# sparrow-though-jack.net
KiCad netlist of a schematic drawn in EAGLE
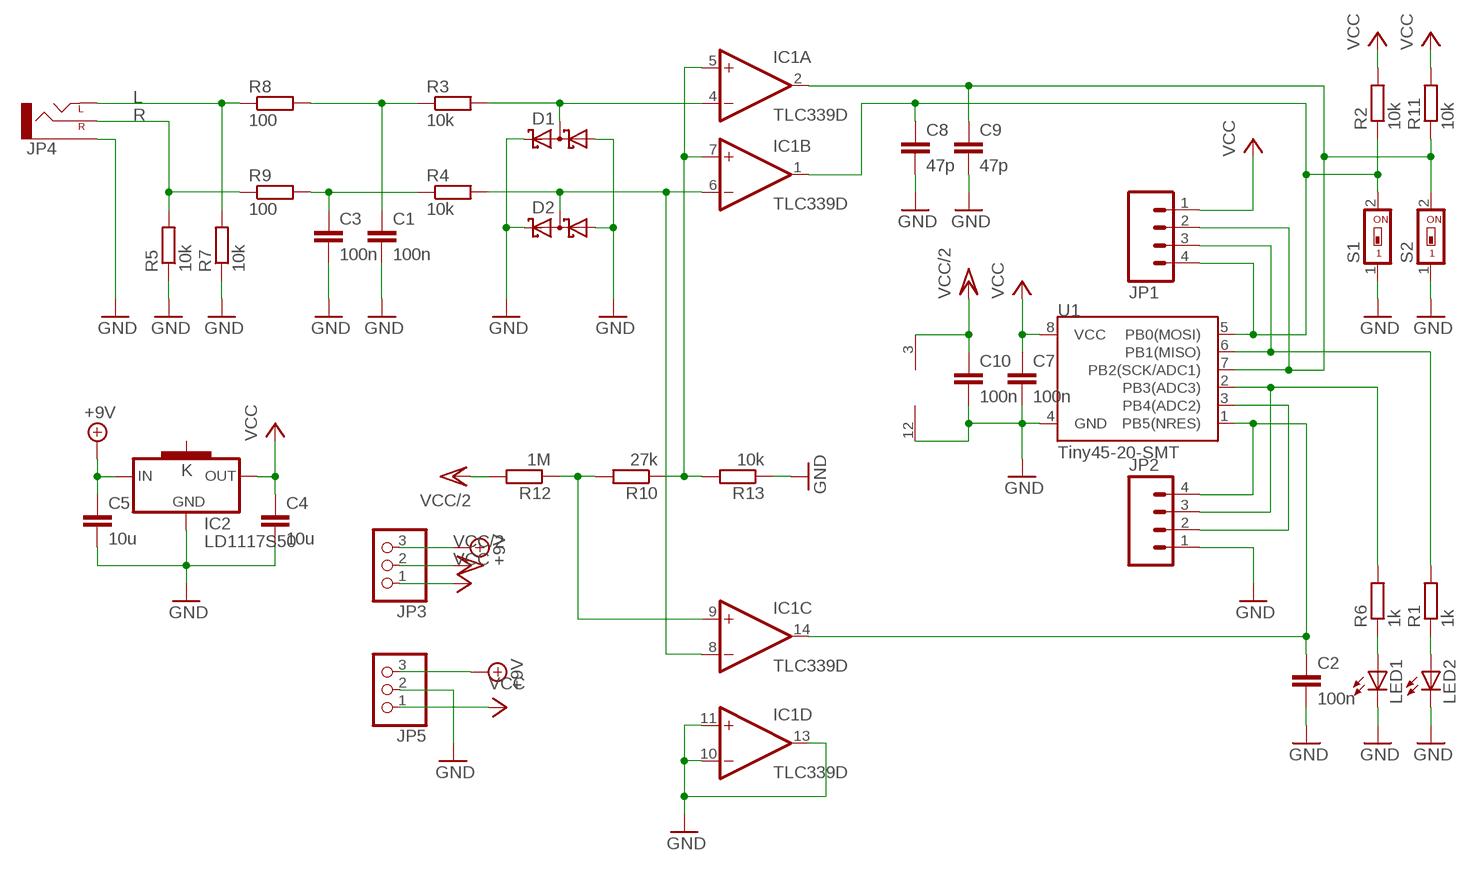
[diagram p0: schematic, sheet 1]

(export (version "E")
  (design (tool "Eeschema 10.0.6"))
  (components
    (comp (ref "C1")
      (value "100n")
      (footprint "eagle-import:C0805K")
      (libsource (lib "eagle-import") (part "C-EUC0805K"))
    )
    (comp (ref "C2")
      (value "100n")
      (footprint "eagle-import:C0805K")
      (libsource (lib "eagle-import") (part "C-EUC0805K"))
    )
    (comp (ref "C3")
      (value "100n")
      (footprint "eagle-import:C0805K")
      (libsource (lib "eagle-import") (part "C-EUC0805K"))
    )
    (comp (ref "C4")
      (value "10u")
      (footprint "eagle-import:C0805K")
      (libsource (lib "eagle-import") (part "C-EUC0805K"))
    )
    (comp (ref "C5")
      (value "10u")
      (footprint "eagle-import:C0805K")
      (libsource (lib "eagle-import") (part "C-EUC0805K"))
    )
    (comp (ref "C7")
      (value "100n")
      (footprint "eagle-import:C0805K")
      (libsource (lib "eagle-import") (part "C-EUC0805K"))
    )
    (comp (ref "C8")
      (value "47p")
      (footprint "eagle-import:C0805K")
      (libsource (lib "eagle-import") (part "C-EUC0805K"))
    )
    (comp (ref "C9")
      (value "47p")
      (footprint "eagle-import:C0805K")
      (libsource (lib "eagle-import") (part "C-EUC0805K"))
    )
    (comp (ref "C10")
      (value "100n")
      (footprint "eagle-import:C0805K")
      (libsource (lib "eagle-import") (part "C-EUC0805K"))
    )
    (comp (ref "D1")
      (value "BAT54S")
      (footprint "eagle-import:SOT23")
      (libsource (lib "eagle-import") (part "BAT54S"))
    )
    (comp (ref "D2")
      (value "BAT54S")
      (footprint "eagle-import:SOT23")
      (libsource (lib "eagle-import") (part "BAT54S"))
    )
    (comp (ref "IC1")
      (value "TLC339D")
      (footprint "eagle-import:SO14")
      (libsource (lib "eagle-import") (part "TLC339D"))
    )
    (comp (ref "IC2")
      (value "LD1117S50")
      (footprint "eagle-import:SOT223")
      (libsource (lib "eagle-import") (part "LD1117S50"))
    )
    (comp (ref "JP1")
      (value "M04PTH")
      (footprint "eagle-import:1X04")
      (libsource (lib "eagle-import") (part "M04PTH"))
    )
    (comp (ref "JP2")
      (value "M04PTH")
      (footprint "eagle-import:1X04")
      (libsource (lib "eagle-import") (part "M04PTH"))
    )
    (comp (ref "JP3")
      (value "PINHD-1X3")
      (footprint "eagle-import:1X03")
      (libsource (lib "eagle-import") (part "PINHD-1X3"))
    )
    (comp (ref "JP4")
      (value "AUDIO-JACKPIN-HOLES")
      (footprint "eagle-import:AUDIO-JACK-HOLES")
      (libsource (lib "eagle-import") (part "AUDIO-JACKPIN-HOLES"))
    )
    (comp (ref "JP5")
      (value "PINHD-1X3")
      (footprint "eagle-import:1X03")
      (libsource (lib "eagle-import") (part "PINHD-1X3"))
    )
    (comp (ref "LED1")
      (value "LEDCHIP-LED0805")
      (footprint "eagle-import:CHIP-LED0805")
      (libsource (lib "eagle-import") (part "LEDCHIP-LED0805"))
    )
    (comp (ref "LED2")
      (value "LEDCHIP-LED0805")
      (footprint "eagle-import:CHIP-LED0805")
      (libsource (lib "eagle-import") (part "LEDCHIP-LED0805"))
    )
    (comp (ref "R1")
      (value "1k")
      (footprint "eagle-import:M0805")
      (libsource (lib "eagle-import") (part "R-EU_M0805"))
    )
    (comp (ref "R2")
      (value "10k")
      (footprint "eagle-import:M0805")
      (libsource (lib "eagle-import") (part "R-EU_M0805"))
    )
    (comp (ref "R3")
      (value "10k")
      (footprint "eagle-import:M0805")
      (libsource (lib "eagle-import") (part "R-EU_M0805"))
    )
    (comp (ref "R4")
      (value "10k")
      (footprint "eagle-import:M0805")
      (libsource (lib "eagle-import") (part "R-EU_M0805"))
    )
    (comp (ref "R5")
      (value "10k")
      (footprint "eagle-import:M0805")
      (libsource (lib "eagle-import") (part "R-EU_M0805"))
    )
    (comp (ref "R6")
      (value "1k")
      (footprint "eagle-import:M0805")
      (libsource (lib "eagle-import") (part "R-EU_M0805"))
    )
    (comp (ref "R7")
      (value "10k")
      (footprint "eagle-import:M0805")
      (libsource (lib "eagle-import") (part "R-EU_M0805"))
    )
    (comp (ref "R8")
      (value "100")
      (footprint "eagle-import:M0805")
      (libsource (lib "eagle-import") (part "R-EU_M0805"))
    )
    (comp (ref "R9")
      (value "100")
      (footprint "eagle-import:M0805")
      (libsource (lib "eagle-import") (part "R-EU_M0805"))
    )
    (comp (ref "R10")
      (value "27k")
      (footprint "eagle-import:M0805")
      (libsource (lib "eagle-import") (part "R-EU_M0805"))
    )
    (comp (ref "R11")
      (value "10k")
      (footprint "eagle-import:M0805")
      (libsource (lib "eagle-import") (part "R-EU_M0805"))
    )
    (comp (ref "R12")
      (value "1M")
      (footprint "eagle-import:M0805")
      (libsource (lib "eagle-import") (part "R-EU_M0805"))
    )
    (comp (ref "R13")
      (value "10k")
      (footprint "eagle-import:M0805")
      (libsource (lib "eagle-import") (part "R-EU_M0805"))
    )
    (comp (ref "S1")
      (value "SWS001")
      (footprint "eagle-import:SMS-001")
      (libsource (lib "eagle-import") (part "SWS001"))
    )
    (comp (ref "S2")
      (value "SWS001")
      (footprint "eagle-import:SMS-001")
      (libsource (lib "eagle-import") (part "SWS001"))
    )
    (comp (ref "U1")
      (value "Tiny45-20-SMT")
      (footprint "eagle-import:SO08-EIAJ")
      (libsource (lib "eagle-import") (part "ATTINY45TINY45-20-SMT"))
    )
  )
  (nets
    (net (code "1") (name "+9V") (class "Default")
      (node (ref "C5") (pin "1") (pinfunction "1_1") (pintype "passive"))
      (node (ref "IC2") (pin "3") (pinfunction "IN_3") (pintype "input"))
      (node (ref "JP3") (pin "3") (pinfunction "3_3") (pintype "passive"))
      (node (ref "JP5") (pin "3") (pinfunction "3_3") (pintype "passive"))
    )
    (net (code "2") (name "/L") (class "Default")
      (node (ref "JP4") (pin "L1-") (pinfunction "LEFT_L1-") (pintype "bidirectional"))
      (node (ref "JP4") (pin "L2-") (pinfunction "LEFT_L2-") (pintype "bidirectional"))
      (node (ref "R7") (pin "2") (pinfunction "2_2") (pintype "passive"))
      (node (ref "R8") (pin "1") (pinfunction "1_1") (pintype "passive"))
    )
    (net (code "3") (name "/R") (class "Default")
      (node (ref "JP4") (pin "R+") (pinfunction "RIGHT_R+") (pintype "bidirectional"))
      (node (ref "R5") (pin "2") (pinfunction "2_2") (pintype "passive"))
      (node (ref "R9") (pin "1") (pinfunction "1_1") (pintype "passive"))
    )
    (net (code "4") (name "GND") (class "Default")
      (node (ref "C1") (pin "2") (pinfunction "2_2") (pintype "passive"))
      (node (ref "C10") (pin "2") (pinfunction "2_2") (pintype "passive"))
      (node (ref "C2") (pin "2") (pinfunction "2_2") (pintype "passive"))
      (node (ref "C3") (pin "2") (pinfunction "2_2") (pintype "passive"))
      (node (ref "C4") (pin "2") (pinfunction "2_2") (pintype "passive"))
      (node (ref "C5") (pin "2") (pinfunction "2_2") (pintype "passive"))
      (node (ref "C7") (pin "2") (pinfunction "2_2") (pintype "passive"))
      (node (ref "C8") (pin "2") (pinfunction "2_2") (pintype "passive"))
      (node (ref "C9") (pin "2") (pinfunction "2_2") (pintype "passive"))
      (node (ref "D1") (pin "1") (pinfunction "A1_1") (pintype "passive"))
      (node (ref "D1") (pin "2") (pinfunction "C2_2") (pintype "passive"))
      (node (ref "D2") (pin "1") (pinfunction "A1_1") (pintype "passive"))
      (node (ref "D2") (pin "2") (pinfunction "C2_2") (pintype "passive"))
      (node (ref "IC1") (pin "10") (pinfunction "-IN_10") (pintype "input"))
      (node (ref "IC1") (pin "11") (pinfunction "+IN_11") (pintype "input"))
      (node (ref "IC1") (pin "12") (pinfunction "V-_12") (pintype "power_in"))
      (node (ref "IC1") (pin "13") (pinfunction "OUT_13") (pintype "output"))
      (node (ref "IC2") (pin "1") (pinfunction "GND_1") (pintype "input"))
      (node (ref "JP2") (pin "1") (pinfunction "1_1") (pintype "passive"))
      (node (ref "JP4") (pin "GND") (pinfunction "SLEEVE_GND") (pintype "bidirectional"))
      (node (ref "JP5") (pin "2") (pinfunction "2_2") (pintype "passive"))
      (node (ref "LED1") (pin "C") (pinfunction "C_C") (pintype "passive"))
      (node (ref "LED2") (pin "C") (pinfunction "C_C") (pintype "passive"))
      (node (ref "R13") (pin "1") (pinfunction "1_1") (pintype "passive"))
      (node (ref "R5") (pin "1") (pinfunction "1_1") (pintype "passive"))
      (node (ref "R7") (pin "1") (pinfunction "1_1") (pintype "passive"))
      (node (ref "S1") (pin "1") (pinfunction "1_1") (pintype "passive"))
      (node (ref "S2") (pin "1") (pinfunction "1_1") (pintype "passive"))
      (node (ref "U1") (pin "4") (pinfunction "GND_4") (pintype "bidirectional"))
    )
    (net (code "5") (name "Net-(C1-Pad1)") (class "Default")
      (node (ref "C1") (pin "1") (pinfunction "1_1") (pintype "passive"))
      (node (ref "R3") (pin "1") (pinfunction "1_1") (pintype "passive"))
      (node (ref "R8") (pin "2") (pinfunction "2_2") (pintype "passive"))
    )
    (net (code "6") (name "Net-(C3-Pad1)") (class "Default")
      (node (ref "C3") (pin "1") (pinfunction "1_1") (pintype "passive"))
      (node (ref "R4") (pin "1") (pinfunction "1_1") (pintype "passive"))
      (node (ref "R9") (pin "2") (pinfunction "2_2") (pintype "passive"))
    )
    (net (code "7") (name "Net-(D1-C1A2)") (class "Default")
      (node (ref "D1") (pin "3") (pinfunction "C1A2_3") (pintype "passive"))
      (node (ref "IC1") (pin "4") (pinfunction "-IN_4") (pintype "input"))
      (node (ref "R3") (pin "2") (pinfunction "2_2") (pintype "passive"))
    )
    (net (code "8") (name "Net-(D2-C1A2)") (class "Default")
      (node (ref "D2") (pin "3") (pinfunction "C1A2_3") (pintype "passive"))
      (node (ref "IC1") (pin "6") (pinfunction "-IN_6") (pintype "input"))
      (node (ref "IC1") (pin "8") (pinfunction "-IN_8") (pintype "input"))
      (node (ref "R4") (pin "2") (pinfunction "2_2") (pintype "passive"))
    )
    (net (code "9") (name "Net-(IC1A-+IN)") (class "Default")
      (node (ref "IC1") (pin "5") (pinfunction "+IN_5") (pintype "input"))
      (node (ref "IC1") (pin "7") (pinfunction "+IN_7") (pintype "input"))
      (node (ref "R10") (pin "1") (pinfunction "1_1") (pintype "passive"))
      (node (ref "R13") (pin "2") (pinfunction "2_2") (pintype "passive"))
    )
    (net (code "10") (name "Net-(IC1A-OUT)") (class "Default")
      (node (ref "C9") (pin "1") (pinfunction "1_1") (pintype "passive"))
      (node (ref "IC1") (pin "2") (pinfunction "OUT_2") (pintype "output"))
      (node (ref "JP1") (pin "2") (pinfunction "2_2") (pintype "passive"))
      (node (ref "R11") (pin "1") (pinfunction "1_1") (pintype "passive"))
      (node (ref "S2") (pin "2") (pinfunction "2_2") (pintype "passive"))
      (node (ref "U1") (pin "7") (pinfunction "PB2(SCK/ADC1)_7") (pintype "bidirectional"))
    )
    (net (code "11") (name "Net-(IC1B-OUT)") (class "Default")
      (node (ref "C8") (pin "1") (pinfunction "1_1") (pintype "passive"))
      (node (ref "IC1") (pin "1") (pinfunction "OUT_1") (pintype "output"))
      (node (ref "JP1") (pin "4") (pinfunction "4_4") (pintype "passive"))
      (node (ref "R2") (pin "1") (pinfunction "1_1") (pintype "passive"))
      (node (ref "S1") (pin "2") (pinfunction "2_2") (pintype "passive"))
      (node (ref "U1") (pin "5") (pinfunction "PB0(MOSI)_5") (pintype "bidirectional"))
    )
    (net (code "12") (name "Net-(IC1C-+IN)") (class "Default")
      (node (ref "IC1") (pin "9") (pinfunction "+IN_9") (pintype "input"))
      (node (ref "R10") (pin "2") (pinfunction "2_2") (pintype "passive"))
      (node (ref "R12") (pin "1") (pinfunction "1_1") (pintype "passive"))
    )
    (net (code "13") (name "Net-(IC1C-OUT)") (class "Default")
      (node (ref "C2") (pin "1") (pinfunction "1_1") (pintype "passive"))
      (node (ref "IC1") (pin "14") (pinfunction "OUT_14") (pintype "output"))
      (node (ref "JP2") (pin "4") (pinfunction "4_4") (pintype "passive"))
      (node (ref "U1") (pin "1") (pinfunction "PB5(NRES)_1") (pintype "bidirectional"))
    )
    (net (code "14") (name "Net-(LED1-PadA)") (class "Default")
      (node (ref "LED1") (pin "A") (pinfunction "A_A") (pintype "passive"))
      (node (ref "R6") (pin "1") (pinfunction "1_1") (pintype "passive"))
    )
    (net (code "15") (name "Net-(LED2-PadA)") (class "Default")
      (node (ref "LED2") (pin "A") (pinfunction "A_A") (pintype "passive"))
      (node (ref "R1") (pin "1") (pinfunction "1_1") (pintype "passive"))
    )
    (net (code "16") (name "Net-(U1-PB1(MISO))") (class "Default")
      (node (ref "JP1") (pin "3") (pinfunction "3_3") (pintype "passive"))
      (node (ref "R1") (pin "2") (pinfunction "2_2") (pintype "passive"))
      (node (ref "U1") (pin "6") (pinfunction "PB1(MISO)_6") (pintype "bidirectional"))
    )
    (net (code "17") (name "Net-(U1-PB3(ADC3))") (class "Default")
      (node (ref "JP2") (pin "3") (pinfunction "3_3") (pintype "passive"))
      (node (ref "R6") (pin "2") (pinfunction "2_2") (pintype "passive"))
      (node (ref "U1") (pin "2") (pinfunction "PB3(ADC3)_2") (pintype "bidirectional"))
    )
    (net (code "18") (name "Net-(U1-PB4(ADC2))") (class "Default")
      (node (ref "JP2") (pin "2") (pinfunction "2_2") (pintype "passive"))
      (node (ref "U1") (pin "3") (pinfunction "PB4(ADC2)_3") (pintype "bidirectional"))
    )
    (net (code "19") (name "VCC") (class "Default")
      (node (ref "C4") (pin "1") (pinfunction "1_1") (pintype "passive"))
      (node (ref "C7") (pin "1") (pinfunction "1_1") (pintype "passive"))
      (node (ref "IC2") (pin "2") (pinfunction "OUT_2") (pintype "passive"))
      (node (ref "JP1") (pin "1") (pinfunction "1_1") (pintype "passive"))
      (node (ref "JP3") (pin "1") (pinfunction "1_1") (pintype "passive"))
      (node (ref "JP5") (pin "1") (pinfunction "1_1") (pintype "passive"))
      (node (ref "R11") (pin "2") (pinfunction "2_2") (pintype "passive"))
      (node (ref "R2") (pin "2") (pinfunction "2_2") (pintype "passive"))
      (node (ref "U1") (pin "8") (pinfunction "VCC_8") (pintype "bidirectional"))
    )
    (net (code "20") (name "VCC{slash}2") (class "Default")
      (node (ref "C10") (pin "1") (pinfunction "1_1") (pintype "passive"))
      (node (ref "IC1") (pin "3") (pinfunction "V+_3") (pintype "power_in"))
      (node (ref "JP3") (pin "2") (pinfunction "2_2") (pintype "passive"))
      (node (ref "R12") (pin "2") (pinfunction "2_2") (pintype "passive"))
    )
    (net (code "21") (name "unconnected-(IC2-K-Pad4)") (class "Default")
      (node (ref "IC2") (pin "4") (pinfunction "K_4") (pintype "passive"))
    )
  )
)
